# PCB.net
KiCad netlist of a schematic drawn in Altium Designer
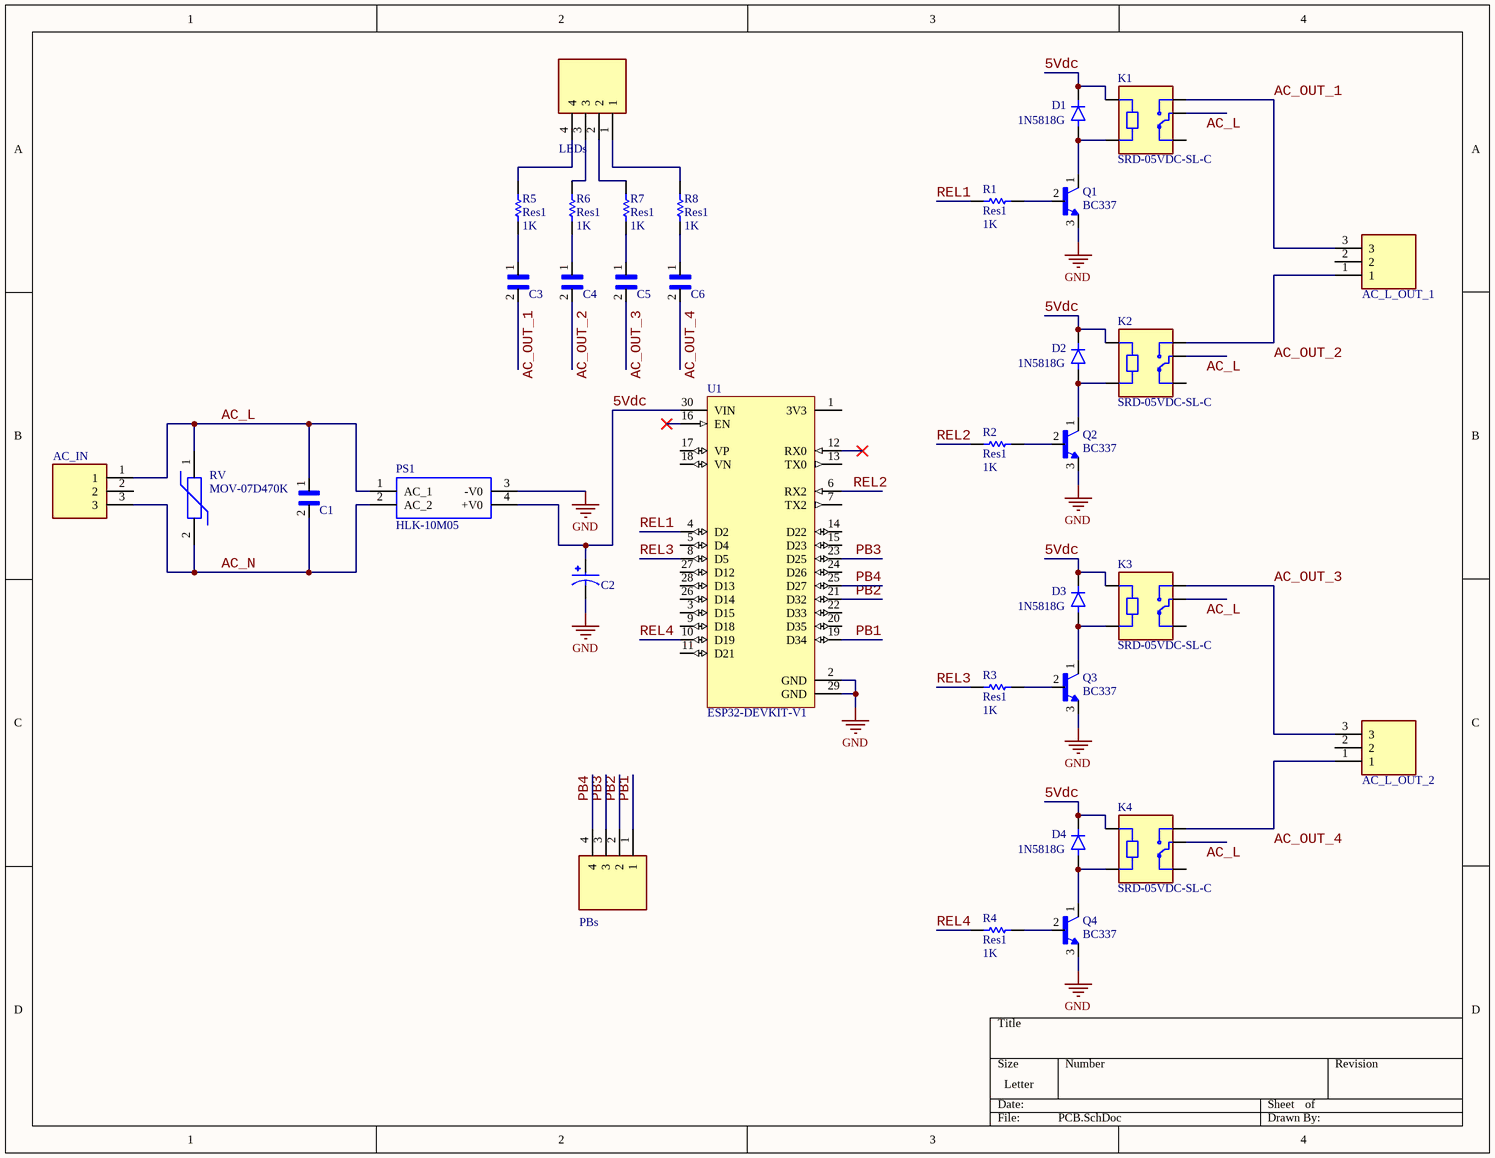
[diagram p0: PCB.SchDoc]

(export (version "E")
  (design (tool "Eeschema 10.0.6"))
  (components
    (comp (ref "AC_IN")
      (value "TB006-508-03BE")
      (footprint "CUI_TB006-508-03BE")
      (description "2~24 Poles, Screw Type, Horizontal, 5.08 Pitch, 26~14 (AWG), Terminal Block Connector")
      (fields (field (name "MF") "CUI Devices"))
      (libsource (lib "") (part "TB006-508-03BE_1"))
    )
    (comp (ref "AC_L_OUT_1")
      (value "TB006-508-03BE")
      (footprint "CUI_TB006-508-03BE")
      (description "2~24 Poles, Screw Type, Horizontal, 5.08 Pitch, 26~14 (AWG), Terminal Block Connector")
      (fields (field (name "MF") "CUI Devices"))
      (libsource (lib "TB006-508-03BE") (part "TB006-508-03BE"))
    )
    (comp (ref "AC_L_OUT_2")
      (value "TB006-508-03BE")
      (footprint "CUI_TB006-508-03BE")
      (description "2~24 Poles, Screw Type, Horizontal, 5.08 Pitch, 26~14 (AWG), Terminal Block Connector")
      (fields (field (name "MF") "CUI Devices"))
      (libsource (lib "TB006-508-03BE") (part "TB006-508-03BE"))
    )
    (comp (ref "C1")
      (value "ECQE4123KFW")
      (footprint "CAPRR750W60L1030T440H1250")
      (libsource (lib "ECQE4123KFW") (part "ECQE4123KFW"))
    )
    (comp (ref "C2")
      (value "25YXG220MEFC6.3X11")
      (footprint "CAPPRD250W50D630H1250")
      (fields (field (name "MF") "Rubycon"))
      (libsource (lib "25YXG220MEFC6.3X11") (part "25YXG220MEFC6.3X11"))
    )
    (comp (ref "C3")
      (value "ECQE4123KFW")
      (footprint "CAPRR750W60L1030T440H1250")
      (libsource (lib "ECQE4123KFW") (part "ECQE4123KFW"))
    )
    (comp (ref "C4")
      (value "ECQE4123KFW")
      (footprint "CAPRR750W60L1030T440H1250")
      (libsource (lib "ECQE4123KFW") (part "ECQE4123KFW"))
    )
    (comp (ref "C5")
      (value "ECQE4123KFW")
      (footprint "CAPRR750W60L1030T440H1250")
      (libsource (lib "ECQE4123KFW") (part "ECQE4123KFW"))
    )
    (comp (ref "C6")
      (value "ECQE4123KFW")
      (footprint "CAPRR750W60L1030T440H1250")
      (libsource (lib "ECQE4123KFW") (part "ECQE4123KFW"))
    )
    (comp (ref "D1")
      (value "1N5818G")
      (footprint "DIOAD1036W78L470D235")
      (description "Diode Schottky 30 V 1A Through Hole Axial")
      (fields (field (name "MF") "ON Semiconductor"))
      (libsource (lib "1N5818G") (part "1N5818G"))
    )
    (comp (ref "D2")
      (value "1N5818G")
      (footprint "DIOAD1036W78L470D235")
      (description "Diode Schottky 30 V 1A Through Hole Axial")
      (fields (field (name "MF") "ON Semiconductor"))
      (libsource (lib "1N5818G") (part "1N5818G"))
    )
    (comp (ref "D3")
      (value "1N5818G")
      (footprint "DIOAD1036W78L470D235")
      (description "Diode Schottky 30 V 1A Through Hole Axial")
      (fields (field (name "MF") "ON Semiconductor"))
      (libsource (lib "1N5818G") (part "1N5818G"))
    )
    (comp (ref "D4")
      (value "1N5818G")
      (footprint "DIOAD1036W78L470D235")
      (description "Diode Schottky 30 V 1A Through Hole Axial")
      (fields (field (name "MF") "ON Semiconductor"))
      (libsource (lib "1N5818G") (part "1N5818G"))
    )
    (comp (ref "K1")
      (value "SRD-05VDC-SL-C")
      (footprint "RELAY_SRD-05VDC-SL-C")
      (fields (field (name "MF") "Songle Relay"))
      (libsource (lib "SRD-05VDC-SL-C") (part "SRD-05VDC-SL-C"))
    )
    (comp (ref "K2")
      (value "SRD-05VDC-SL-C")
      (footprint "RELAY_SRD-05VDC-SL-C")
      (fields (field (name "MF") "Songle Relay"))
      (libsource (lib "SRD-05VDC-SL-C") (part "SRD-05VDC-SL-C"))
    )
    (comp (ref "K3")
      (value "SRD-05VDC-SL-C")
      (footprint "RELAY_SRD-05VDC-SL-C")
      (fields (field (name "MF") "Songle Relay"))
      (libsource (lib "SRD-05VDC-SL-C") (part "SRD-05VDC-SL-C"))
    )
    (comp (ref "K4")
      (value "SRD-05VDC-SL-C")
      (footprint "RELAY_SRD-05VDC-SL-C")
      (fields (field (name "MF") "Songle Relay"))
      (libsource (lib "SRD-05VDC-SL-C") (part "SRD-05VDC-SL-C"))
    )
    (comp (ref "LEDs")
      (value "TB007-508-04BE")
      (footprint "CUI_TB007-508-04BE")
      (description "2~24 Poles, Screw Type, Horizontal, 5.08 Pitch, 24~12 (AWG), Terminal Block Connector")
      (fields (field (name "MF") "CUI Devices"))
      (libsource (lib "") (part "TB007-508-04BE_1"))
    )
    (comp (ref "PBs")
      (value "TB007-508-04BE")
      (footprint "CUI_TB007-508-04BE")
      (description "2~24 Poles, Screw Type, Horizontal, 5.08 Pitch, 24~12 (AWG), Terminal Block Connector")
      (fields (field (name "MF") "CUI Devices"))
      (libsource (lib "TB007-508-04BE") (part "TB007-508-04BE"))
    )
    (comp (ref "PS1")
      (value "HLK-10M05")
      (footprint "HLK10M05")
      (description "10W Ultra-Compact Power Module")
      (fields (field (name "MF") "Hi-link"))
      (libsource (lib "HLK-10M05") (part "HLK-10M05"))
    )
    (comp (ref "Q1")
      (value "BC337")
      (footprint "TO92250P510H770-3")
      (description "TO-92, 50V, 0.8A, NPN Bipolar Transistor")
      (fields (field (name "MF") "Taiwan Semiconductor") (field (name "MP") "BC337-16 A1"))
      (libsource (lib "BC337-16_A1") (part "BC337-16_A1"))
    )
    (comp (ref "Q2")
      (value "BC337")
      (footprint "TO92250P510H770-3")
      (description "TO-92, 50V, 0.8A, NPN Bipolar Transistor")
      (fields (field (name "MF") "Taiwan Semiconductor") (field (name "MP") "BC337-16 A1"))
      (libsource (lib "BC337-16_A1") (part "BC337-16_A1"))
    )
    (comp (ref "Q3")
      (value "BC337")
      (footprint "TO92250P510H770-3")
      (description "TO-92, 50V, 0.8A, NPN Bipolar Transistor")
      (fields (field (name "MF") "Taiwan Semiconductor") (field (name "MP") "BC337-16 A1"))
      (libsource (lib "BC337-16_A1") (part "BC337-16_A1"))
    )
    (comp (ref "Q4")
      (value "BC337")
      (footprint "TO92250P510H770-3")
      (description "TO-92, 50V, 0.8A, NPN Bipolar Transistor")
      (fields (field (name "MF") "Taiwan Semiconductor") (field (name "MP") "BC337-16 A1"))
      (libsource (lib "BC337-16_A1") (part "BC337-16_A1"))
    )
    (comp (ref "R1")
      (value "Res1")
      (footprint "AXIAL-0.3")
      (description "Resistor")
      (fields (field (name "ALTIUM_VALUE") "1K") (field (name "PUBLISHER") "Altium Limited"))
      (libsource (lib "Miscellaneous Devices") (part "Res1"))
    )
    (comp (ref "R2")
      (value "Res1")
      (footprint "AXIAL-0.3")
      (description "Resistor")
      (fields (field (name "ALTIUM_VALUE") "1K") (field (name "PUBLISHER") "Altium Limited"))
      (libsource (lib "Miscellaneous Devices") (part "Res1"))
    )
    (comp (ref "R3")
      (value "Res1")
      (footprint "AXIAL-0.3")
      (description "Resistor")
      (fields (field (name "ALTIUM_VALUE") "1K") (field (name "PUBLISHER") "Altium Limited"))
      (libsource (lib "Miscellaneous Devices") (part "Res1"))
    )
    (comp (ref "R4")
      (value "Res1")
      (footprint "AXIAL-0.3")
      (description "Resistor")
      (fields (field (name "ALTIUM_VALUE") "1K") (field (name "PUBLISHER") "Altium Limited"))
      (libsource (lib "Miscellaneous Devices") (part "Res1"))
    )
    (comp (ref "R5")
      (value "Res1")
      (footprint "AXIAL-0.3")
      (description "Resistor")
      (fields (field (name "ALTIUM_VALUE") "1K") (field (name "PUBLISHER") "Altium Limited"))
      (libsource (lib "Miscellaneous Devices") (part "Res1"))
    )
    (comp (ref "R6")
      (value "Res1")
      (footprint "AXIAL-0.3")
      (description "Resistor")
      (fields (field (name "ALTIUM_VALUE") "1K") (field (name "PUBLISHER") "Altium Limited"))
      (libsource (lib "Miscellaneous Devices") (part "Res1"))
    )
    (comp (ref "R7")
      (value "Res1")
      (footprint "AXIAL-0.3")
      (description "Resistor")
      (fields (field (name "ALTIUM_VALUE") "1K") (field (name "PUBLISHER") "Altium Limited"))
      (libsource (lib "Miscellaneous Devices") (part "Res1"))
    )
    (comp (ref "R8")
      (value "Res1")
      (footprint "AXIAL-0.3")
      (description "Resistor")
      (fields (field (name "ALTIUM_VALUE") "1K") (field (name "PUBLISHER") "Altium Limited"))
      (libsource (lib "Miscellaneous Devices") (part "Res1"))
    )
    (comp (ref "RV")
      (value "MOV-07D470K")
      (footprint "MOV-07DXXXK(3.9T)")
      (description "47V 250A Varistor 1 Circuit Through Hole Disc 7mm")
      (fields (field (name "MF") "Bourns"))
      (libsource (lib "MOV-07D470K") (part "MOV-07D470K"))
    )
    (comp (ref "U1")
      (value "ESP32-DEVKIT-V1")
      (footprint "ESP32-DEVKIT-V1")
      (libsource (lib "SEM5 - EDR project") (part "ESP32-DEVKIT-V1"))
    )
  )
  (nets
    (net (code "1") (name "/5Vdc") (class "Default")
      (node (ref "C2") (pin "P") (pinfunction "P_P") (pintype "passive"))
      (node (ref "D1") (pin "C") (pinfunction "K_C") (pintype "passive"))
      (node (ref "D2") (pin "C") (pinfunction "K_C") (pintype "passive"))
      (node (ref "D3") (pin "C") (pinfunction "K_C") (pintype "passive"))
      (node (ref "D4") (pin "C") (pinfunction "K_C") (pintype "passive"))
      (node (ref "K1") (pin "A1") (pinfunction "A1_A1") (pintype "passive"))
      (node (ref "K2") (pin "A1") (pinfunction "A1_A1") (pintype "passive"))
      (node (ref "K3") (pin "A1") (pinfunction "A1_A1") (pintype "passive"))
      (node (ref "K4") (pin "A1") (pinfunction "A1_A1") (pintype "passive"))
      (node (ref "PS1") (pin "4") (pinfunction "+V0_4") (pintype "power_in"))
      (node (ref "U1") (pin "30") (pinfunction "VIN_30") (pintype "power_in"))
    )
    (net (code "2") (name "/AC_L") (class "Default")
      (node (ref "AC_IN") (pin "1") (pinfunction "1_1") (pintype "passive"))
      (node (ref "C1") (pin "1") (pinfunction "1_1") (pintype "passive"))
      (node (ref "K1") (pin "COM") (pinfunction "COM_COM") (pintype "passive"))
      (node (ref "K2") (pin "COM") (pinfunction "COM_COM") (pintype "passive"))
      (node (ref "K3") (pin "COM") (pinfunction "COM_COM") (pintype "passive"))
      (node (ref "K4") (pin "COM") (pinfunction "COM_COM") (pintype "passive"))
      (node (ref "PS1") (pin "1") (pinfunction "AC_1_1") (pintype "power_in"))
      (node (ref "RV") (pin "1") (pinfunction "1_1") (pintype "power_in"))
    )
    (net (code "3") (name "/AC_N") (class "Default")
      (node (ref "AC_IN") (pin "3") (pinfunction "3_3") (pintype "passive"))
      (node (ref "C1") (pin "2") (pinfunction "2_2") (pintype "passive"))
      (node (ref "PS1") (pin "2") (pinfunction "AC_2_2") (pintype "power_in"))
      (node (ref "RV") (pin "2") (pinfunction "2_2") (pintype "power_in"))
    )
    (net (code "4") (name "/AC_OUT_1") (class "Default")
      (node (ref "AC_L_OUT_1") (pin "3") (pinfunction "3_3") (pintype "passive"))
      (node (ref "C3") (pin "2") (pinfunction "2_2") (pintype "passive"))
      (node (ref "K1") (pin "NO") (pinfunction "NO_NO") (pintype "passive"))
    )
    (net (code "5") (name "/AC_OUT_2") (class "Default")
      (node (ref "AC_L_OUT_1") (pin "1") (pinfunction "1_1") (pintype "passive"))
      (node (ref "C4") (pin "2") (pinfunction "2_2") (pintype "passive"))
      (node (ref "K2") (pin "NO") (pinfunction "NO_NO") (pintype "passive"))
    )
    (net (code "6") (name "/AC_OUT_3") (class "Default")
      (node (ref "AC_L_OUT_2") (pin "3") (pinfunction "3_3") (pintype "passive"))
      (node (ref "C5") (pin "2") (pinfunction "2_2") (pintype "passive"))
      (node (ref "K3") (pin "NO") (pinfunction "NO_NO") (pintype "passive"))
    )
    (net (code "7") (name "/AC_OUT_4") (class "Default")
      (node (ref "AC_L_OUT_2") (pin "1") (pinfunction "1_1") (pintype "passive"))
      (node (ref "C6") (pin "2") (pinfunction "2_2") (pintype "passive"))
      (node (ref "K4") (pin "NO") (pinfunction "NO_NO") (pintype "passive"))
    )
    (net (code "8") (name "/PB1") (class "Default")
      (node (ref "PBs") (pin "1") (pinfunction "1_1") (pintype "passive"))
      (node (ref "U1") (pin "19") (pinfunction "D34_19") (pintype "bidirectional"))
    )
    (net (code "9") (name "/PB2") (class "Default")
      (node (ref "PBs") (pin "2") (pinfunction "2_2") (pintype "passive"))
      (node (ref "U1") (pin "21") (pinfunction "D32_21") (pintype "bidirectional"))
    )
    (net (code "10") (name "/PB3") (class "Default")
      (node (ref "PBs") (pin "3") (pinfunction "3_3") (pintype "passive"))
      (node (ref "U1") (pin "23") (pinfunction "D25_23") (pintype "bidirectional"))
    )
    (net (code "11") (name "/PB4") (class "Default")
      (node (ref "PBs") (pin "4") (pinfunction "4_4") (pintype "passive"))
      (node (ref "U1") (pin "25") (pinfunction "D27_25") (pintype "bidirectional"))
    )
    (net (code "12") (name "/REL1") (class "Default")
      (node (ref "R1") (pin "1") (pinfunction "1_1") (pintype "passive"))
      (node (ref "U1") (pin "4") (pinfunction "D2_4") (pintype "bidirectional"))
    )
    (net (code "13") (name "/REL2") (class "Default")
      (node (ref "R2") (pin "1") (pinfunction "1_1") (pintype "passive"))
      (node (ref "U1") (pin "6") (pinfunction "RX2_6") (pintype "input"))
    )
    (net (code "14") (name "/REL3") (class "Default")
      (node (ref "R3") (pin "1") (pinfunction "1_1") (pintype "passive"))
      (node (ref "U1") (pin "8") (pinfunction "D5_8") (pintype "bidirectional"))
    )
    (net (code "15") (name "/REL4") (class "Default")
      (node (ref "R4") (pin "1") (pinfunction "1_1") (pintype "passive"))
      (node (ref "U1") (pin "10") (pinfunction "D19_10") (pintype "bidirectional"))
    )
    (net (code "16") (name "GND") (class "Default")
      (node (ref "C2") (pin "N") (pinfunction "N_N") (pintype "passive"))
      (node (ref "PS1") (pin "3") (pinfunction "-V0_3") (pintype "power_in"))
      (node (ref "Q1") (pin "3") (pinfunction "E_3") (pintype "passive"))
      (node (ref "Q2") (pin "3") (pinfunction "E_3") (pintype "passive"))
      (node (ref "Q3") (pin "3") (pinfunction "E_3") (pintype "passive"))
      (node (ref "Q4") (pin "3") (pinfunction "E_3") (pintype "passive"))
      (node (ref "U1") (pin "2") (pinfunction "GND_2") (pintype "power_in"))
      (node (ref "U1") (pin "29") (pinfunction "GND_29") (pintype "power_in"))
    )
    (net (code "17") (name "Net-(C3-Pad1)") (class "Default")
      (node (ref "C3") (pin "1") (pinfunction "1_1") (pintype "passive"))
      (node (ref "R5") (pin "1") (pinfunction "1_1") (pintype "passive"))
    )
    (net (code "18") (name "Net-(C4-Pad1)") (class "Default")
      (node (ref "C4") (pin "1") (pinfunction "1_1") (pintype "passive"))
      (node (ref "R6") (pin "1") (pinfunction "1_1") (pintype "passive"))
    )
    (net (code "19") (name "Net-(C5-Pad1)") (class "Default")
      (node (ref "C5") (pin "1") (pinfunction "1_1") (pintype "passive"))
      (node (ref "R7") (pin "1") (pinfunction "1_1") (pintype "passive"))
    )
    (net (code "20") (name "Net-(C6-Pad1)") (class "Default")
      (node (ref "C6") (pin "1") (pinfunction "1_1") (pintype "passive"))
      (node (ref "R8") (pin "1") (pinfunction "1_1") (pintype "passive"))
    )
    (net (code "21") (name "Net-(LEDs-Pad1)") (class "Default")
      (node (ref "LEDs") (pin "1") (pinfunction "1_1") (pintype "passive"))
      (node (ref "R8") (pin "2") (pinfunction "2_2") (pintype "passive"))
    )
    (net (code "22") (name "Net-(LEDs-Pad2)") (class "Default")
      (node (ref "LEDs") (pin "2") (pinfunction "2_2") (pintype "passive"))
      (node (ref "R7") (pin "2") (pinfunction "2_2") (pintype "passive"))
    )
    (net (code "23") (name "Net-(LEDs-Pad3)") (class "Default")
      (node (ref "LEDs") (pin "3") (pinfunction "3_3") (pintype "passive"))
      (node (ref "R6") (pin "2") (pinfunction "2_2") (pintype "passive"))
    )
    (net (code "24") (name "Net-(LEDs-Pad4)") (class "Default")
      (node (ref "LEDs") (pin "4") (pinfunction "4_4") (pintype "passive"))
      (node (ref "R5") (pin "2") (pinfunction "2_2") (pintype "passive"))
    )
    (net (code "25") (name "Net-(Q1-B)") (class "Default")
      (node (ref "Q1") (pin "2") (pinfunction "B_2") (pintype "passive"))
      (node (ref "R1") (pin "2") (pinfunction "2_2") (pintype "passive"))
    )
    (net (code "26") (name "Net-(Q1-C)") (class "Default")
      (node (ref "D1") (pin "A") (pinfunction "A_A") (pintype "passive"))
      (node (ref "K1") (pin "A2") (pinfunction "A2_A2") (pintype "passive"))
      (node (ref "Q1") (pin "1") (pinfunction "C_1") (pintype "passive"))
    )
    (net (code "27") (name "Net-(Q2-B)") (class "Default")
      (node (ref "Q2") (pin "2") (pinfunction "B_2") (pintype "passive"))
      (node (ref "R2") (pin "2") (pinfunction "2_2") (pintype "passive"))
    )
    (net (code "28") (name "Net-(Q2-C)") (class "Default")
      (node (ref "D2") (pin "A") (pinfunction "A_A") (pintype "passive"))
      (node (ref "K2") (pin "A2") (pinfunction "A2_A2") (pintype "passive"))
      (node (ref "Q2") (pin "1") (pinfunction "C_1") (pintype "passive"))
    )
    (net (code "29") (name "Net-(Q3-B)") (class "Default")
      (node (ref "Q3") (pin "2") (pinfunction "B_2") (pintype "passive"))
      (node (ref "R3") (pin "2") (pinfunction "2_2") (pintype "passive"))
    )
    (net (code "30") (name "Net-(Q3-C)") (class "Default")
      (node (ref "D3") (pin "A") (pinfunction "A_A") (pintype "passive"))
      (node (ref "K3") (pin "A2") (pinfunction "A2_A2") (pintype "passive"))
      (node (ref "Q3") (pin "1") (pinfunction "C_1") (pintype "passive"))
    )
    (net (code "31") (name "Net-(Q4-B)") (class "Default")
      (node (ref "Q4") (pin "2") (pinfunction "B_2") (pintype "passive"))
      (node (ref "R4") (pin "2") (pinfunction "2_2") (pintype "passive"))
    )
    (net (code "32") (name "Net-(Q4-C)") (class "Default")
      (node (ref "D4") (pin "A") (pinfunction "A_A") (pintype "passive"))
      (node (ref "K4") (pin "A2") (pinfunction "A2_A2") (pintype "passive"))
      (node (ref "Q4") (pin "1") (pinfunction "C_1") (pintype "passive"))
    )
    (net (code "33") (name "unconnected-(AC_IN-Pad2)") (class "Default")
      (node (ref "AC_IN") (pin "2") (pinfunction "2_2") (pintype "passive"))
    )
    (net (code "34") (name "unconnected-(AC_L_OUT_1-Pad2)") (class "Default")
      (node (ref "AC_L_OUT_1") (pin "2") (pinfunction "2_2") (pintype "passive"))
    )
    (net (code "35") (name "unconnected-(AC_L_OUT_2-Pad2)") (class "Default")
      (node (ref "AC_L_OUT_2") (pin "2") (pinfunction "2_2") (pintype "passive"))
    )
    (net (code "36") (name "unconnected-(K1-PadNC)") (class "Default")
      (node (ref "K1") (pin "NC") (pinfunction "NC_NC") (pintype "passive"))
    )
    (net (code "37") (name "unconnected-(K2-PadNC)") (class "Default")
      (node (ref "K2") (pin "NC") (pinfunction "NC_NC") (pintype "passive"))
    )
    (net (code "38") (name "unconnected-(K3-PadNC)") (class "Default")
      (node (ref "K3") (pin "NC") (pinfunction "NC_NC") (pintype "passive"))
    )
    (net (code "39") (name "unconnected-(K4-PadNC)") (class "Default")
      (node (ref "K4") (pin "NC") (pinfunction "NC_NC") (pintype "passive"))
    )
    (net (code "40") (name "unconnected-(U1-3V3-Pad1)") (class "Default")
      (node (ref "U1") (pin "1") (pinfunction "3V3_1") (pintype "power_in"))
    )
    (net (code "41") (name "unconnected-(U1-D4-Pad5)") (class "Default")
      (node (ref "U1") (pin "5") (pinfunction "D4_5") (pintype "bidirectional"))
    )
    (net (code "42") (name "unconnected-(U1-D12-Pad27)") (class "Default")
      (node (ref "U1") (pin "27") (pinfunction "D12_27") (pintype "bidirectional"))
    )
    (net (code "43") (name "unconnected-(U1-D13-Pad28)") (class "Default")
      (node (ref "U1") (pin "28") (pinfunction "D13_28") (pintype "bidirectional"))
    )
    (net (code "44") (name "unconnected-(U1-D14-Pad26)") (class "Default")
      (node (ref "U1") (pin "26") (pinfunction "D14_26") (pintype "bidirectional"))
    )
    (net (code "45") (name "unconnected-(U1-D15-Pad3)") (class "Default")
      (node (ref "U1") (pin "3") (pinfunction "D15_3") (pintype "bidirectional"))
    )
    (net (code "46") (name "unconnected-(U1-D18-Pad9)") (class "Default")
      (node (ref "U1") (pin "9") (pinfunction "D18_9") (pintype "bidirectional"))
    )
    (net (code "47") (name "unconnected-(U1-D21-Pad11)") (class "Default")
      (node (ref "U1") (pin "11") (pinfunction "D21_11") (pintype "bidirectional"))
    )
    (net (code "48") (name "unconnected-(U1-D22-Pad14)") (class "Default")
      (node (ref "U1") (pin "14") (pinfunction "D22_14") (pintype "bidirectional"))
    )
    (net (code "49") (name "unconnected-(U1-D23-Pad15)") (class "Default")
      (node (ref "U1") (pin "15") (pinfunction "D23_15") (pintype "bidirectional"))
    )
    (net (code "50") (name "unconnected-(U1-D26-Pad24)") (class "Default")
      (node (ref "U1") (pin "24") (pinfunction "D26_24") (pintype "bidirectional"))
    )
    (net (code "51") (name "unconnected-(U1-D33-Pad22)") (class "Default")
      (node (ref "U1") (pin "22") (pinfunction "D33_22") (pintype "bidirectional"))
    )
    (net (code "52") (name "unconnected-(U1-D35-Pad20)") (class "Default")
      (node (ref "U1") (pin "20") (pinfunction "D35_20") (pintype "bidirectional"))
    )
    (net (code "53") (name "unconnected-(U1-EN-Pad16)") (class "Default")
      (node (ref "U1") (pin "16") (pinfunction "EN_16") (pintype "input+no_connect"))
    )
    (net (code "54") (name "unconnected-(U1-RX0-Pad12)") (class "Default")
      (node (ref "U1") (pin "12") (pinfunction "RX0_12") (pintype "input+no_connect"))
    )
    (net (code "55") (name "unconnected-(U1-TX0-Pad13)") (class "Default")
      (node (ref "U1") (pin "13") (pinfunction "TX0_13") (pintype "output"))
    )
    (net (code "56") (name "unconnected-(U1-TX2-Pad7)") (class "Default")
      (node (ref "U1") (pin "7") (pinfunction "TX2_7") (pintype "output"))
    )
    (net (code "57") (name "unconnected-(U1-VN-Pad18)") (class "Default")
      (node (ref "U1") (pin "18") (pinfunction "VN_18") (pintype "bidirectional"))
    )
    (net (code "58") (name "unconnected-(U1-VP-Pad17)") (class "Default")
      (node (ref "U1") (pin "17") (pinfunction "VP_17") (pintype "bidirectional"))
    )
  )
)
